# Connectors.net
KiCad netlist of a schematic drawn in Altium Designer
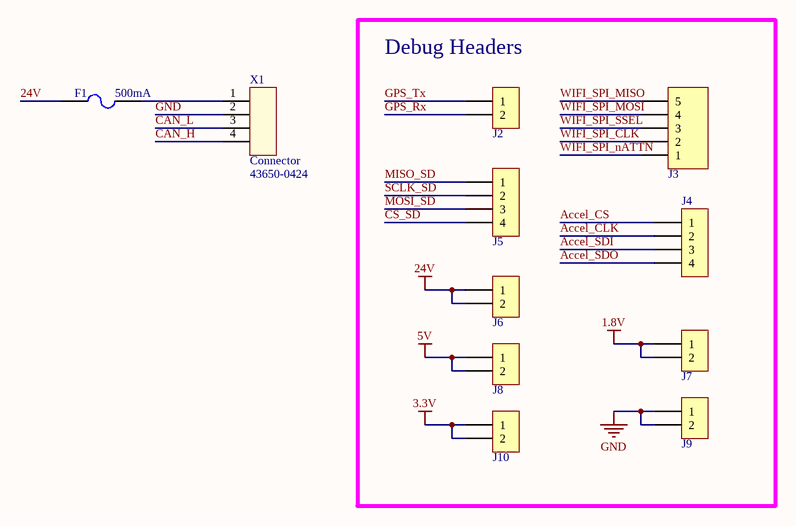
[diagram p0: Connectors.SchDoc]

(export (version "E")
  (design (tool "Eeschema 10.0.6"))
  (components
    (comp (ref "F1")
      (value "500mA")
      (footprint "154_OMNI-BLOK")
      (description "500mA Surface Mount Fuses 453 Series NANO2® Very Fast-Acting Fuse")
      (fields (field (name "PART_NUMBER") "0154010.DR") (field (name "MANUFACTURER") "Littelfuse Inc."))
      (libsource (lib "Fuses") (part "0453.500MR"))
    )
    (comp (ref "J2")
      (value "Header 2")
      (footprint "Connectors:HDR1X2")
      (description "Header, 2-Pin")
      (libsource (lib "Connectors") (part "Header 2"))
    )
    (comp (ref "J3")
      (value "Header, Xbee SPI")
      (footprint "Connectors:HDR1X5")
      (description "Header, 5-Pin")
      (libsource (lib "Connectors") (part "Header 5"))
    )
    (comp (ref "J4")
      (value "Header 4")
      (footprint "Connectors:HDR1X4")
      (description "Header, 4-Pin")
      (libsource (lib "Connectors") (part "Header 4"))
    )
    (comp (ref "J5")
      (value "SD SPI")
      (footprint "Connectors:HDR1X4")
      (description "Header, 4-Pin")
      (libsource (lib "Connectors") (part "Header 4"))
    )
    (comp (ref "J6")
      (value "Header for debugging")
      (footprint "HDR1X2")
      (description "Header, 2-Pin")
      (libsource (lib "Connectors") (part "Header 2"))
    )
    (comp (ref "J7")
      (value "Header for debugging")
      (footprint "HDR1X2")
      (description "Header, 2-Pin")
      (libsource (lib "Connectors") (part "Header 2"))
    )
    (comp (ref "J8")
      (value "Header for debugging")
      (footprint "HDR1X2")
      (description "Header, 2-Pin")
      (libsource (lib "Connectors") (part "Header 2"))
    )
    (comp (ref "J9")
      (value "Header for debugging")
      (footprint "HDR1X2")
      (description "Header, 2-Pin")
      (libsource (lib "Connectors") (part "Header 2"))
    )
    (comp (ref "J10")
      (value "Header for debugging")
      (footprint "HDR1X2")
      (description "Header, 2-Pin")
      (libsource (lib "Connectors") (part "Header 2"))
    )
    (comp (ref "X1")
      (value "Connector")
      (footprint "43650-0400")
      (fields (field (name "MANUFACTURER") "Molex, LLC") (field (name "PART_NUMBER") "43650-0424"))
      (libsource (lib "Connectors") (part "43650-0400"))
    )
  )
  (nets
    (net (code "1") (name "/Accel_CLK") (class "Default")
      (node (ref "J4") (pin "2") (pinfunction "2_2") (pintype "passive"))
    )
    (net (code "2") (name "/Accel_CS") (class "Default")
      (node (ref "J4") (pin "1") (pinfunction "1_1") (pintype "passive"))
    )
    (net (code "3") (name "/Accel_SDI") (class "Default")
      (node (ref "J4") (pin "3") (pinfunction "3_3") (pintype "passive"))
    )
    (net (code "4") (name "/Accel_SDO") (class "Default")
      (node (ref "J4") (pin "4") (pinfunction "4_4") (pintype "passive"))
    )
    (net (code "5") (name "/CAN_H") (class "Default") (node (ref "X1") (pin "4") (pintype "passive")))
    (net (code "6") (name "/CAN_L") (class "Default") (node (ref "X1") (pin "3") (pintype "passive")))
    (net (code "7") (name "/CS_SD") (class "Default")
      (node (ref "J5") (pin "4") (pinfunction "4_4") (pintype "passive"))
    )
    (net (code "8") (name "/GPS_Rx") (class "Default")
      (node (ref "J2") (pin "2") (pinfunction "2_2") (pintype "passive"))
    )
    (net (code "9") (name "/GPS_Tx") (class "Default")
      (node (ref "J2") (pin "1") (pinfunction "1_1") (pintype "passive"))
    )
    (net (code "10") (name "/MISO_SD") (class "Default")
      (node (ref "J5") (pin "1") (pinfunction "1_1") (pintype "passive"))
    )
    (net (code "11") (name "/MOSI_SD") (class "Default")
      (node (ref "J5") (pin "3") (pinfunction "3_3") (pintype "passive"))
    )
    (net (code "12") (name "/SCLK_SD") (class "Default")
      (node (ref "J5") (pin "2") (pinfunction "2_2") (pintype "passive"))
    )
    (net (code "13") (name "/WIFI_SPI_CLK") (class "Default")
      (node (ref "J3") (pin "2") (pinfunction "2_2") (pintype "passive"))
    )
    (net (code "14") (name "/WIFI_SPI_MISO") (class "Default")
      (node (ref "J3") (pin "5") (pinfunction "5_5") (pintype "passive"))
    )
    (net (code "15") (name "/WIFI_SPI_MOSI") (class "Default")
      (node (ref "J3") (pin "4") (pinfunction "4_4") (pintype "passive"))
    )
    (net (code "16") (name "/WIFI_SPI_SSEL") (class "Default")
      (node (ref "J3") (pin "3") (pinfunction "3_3") (pintype "passive"))
    )
    (net (code "17") (name "/WIFI_SPI_nATTN") (class "Default")
      (node (ref "J3") (pin "1") (pinfunction "1_1") (pintype "passive"))
    )
    (net (code "18") (name "1.8V") (class "Default")
      (node (ref "J7") (pin "1") (pinfunction "1_1") (pintype "passive"))
      (node (ref "J7") (pin "2") (pinfunction "2_2") (pintype "passive"))
    )
    (net (code "19") (name "3.3V") (class "Default")
      (node (ref "J10") (pin "1") (pinfunction "1_1") (pintype "passive"))
      (node (ref "J10") (pin "2") (pinfunction "2_2") (pintype "passive"))
    )
    (net (code "20") (name "5V") (class "Default")
      (node (ref "J8") (pin "1") (pinfunction "1_1") (pintype "passive"))
      (node (ref "J8") (pin "2") (pinfunction "2_2") (pintype "passive"))
    )
    (net (code "21") (name "24V") (class "Default")
      (node (ref "F1") (pin "2") (pinfunction "2_2") (pintype "passive"))
      (node (ref "J6") (pin "1") (pinfunction "1_1") (pintype "passive"))
      (node (ref "J6") (pin "2") (pinfunction "2_2") (pintype "passive"))
    )
    (net (code "22") (name "GND") (class "Default")
      (node (ref "J9") (pin "1") (pinfunction "1_1") (pintype "passive"))
      (node (ref "J9") (pin "2") (pinfunction "2_2") (pintype "passive"))
      (node (ref "X1") (pin "2") (pintype "passive"))
    )
    (net (code "23") (name "Net-(F1-Pad1)") (class "Default")
      (node (ref "F1") (pin "1") (pinfunction "1_1") (pintype "passive"))
      (node (ref "X1") (pin "1") (pintype "passive"))
    )
  )
)
